# FTDI.net
KiCad netlist of a schematic drawn in Altium Designer
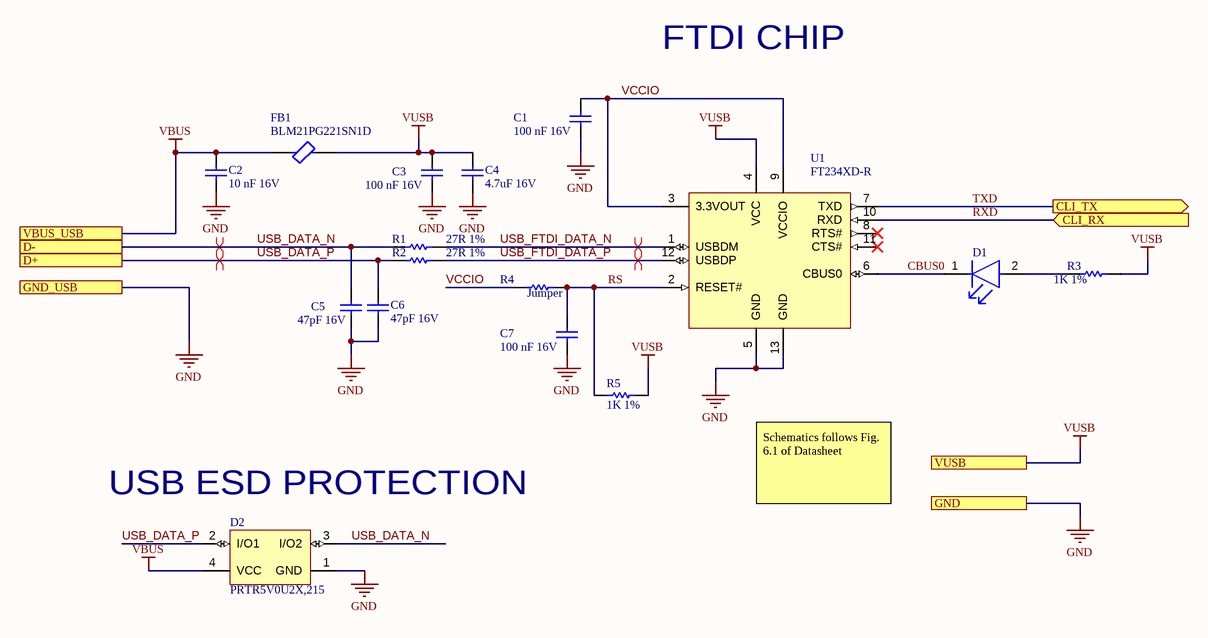
[diagram p0: FTDI.SchDoc]

(export (version "E")
  (design (tool "Eeschema 10.0.6"))
  (components
    (comp (ref "C1")
      (value "100 nF 16V")
      (footprint "CAPC1608X95X40LL15T15")
      (description "VJ0603Y104KXJCW1BC")
      (fields (field (name "MANUFACTURER") "Vitramon"))
      (libsource (lib "Altium Content Vault") (part "CAP"))
    )
    (comp (ref "C2")
      (value "10 nF 16V")
      (footprint "CAPC1608X87X35NL15T15")
      (description "C0603C103K4RACTU")
      (fields (field (name "MANUFACTURER") "Kemet"))
      (libsource (lib "Altium Content Vault") (part "CAP"))
    )
    (comp (ref "C3")
      (value "100 nF 16V")
      (footprint "CAPC1608X95X40LL15T15")
      (description "VJ0603Y104KXJCW1BC")
      (fields (field (name "MANUFACTURER") "Vitramon"))
      (libsource (lib "Altium Content Vault") (part "CAP"))
    )
    (comp (ref "C4")
      (value "4.7uF 16V")
      (footprint "CAPC0805(2012)145_N")
      (description "CAP 4.7uF 16V -20% to +80% 0805 (2012 Metric) Thickness 1.45mm SMD")
      (fields (field (name "TOLERANCE") "-20% to +80%"))
      (libsource (lib "Altium Content Vault") (part "CAP"))
    )
    (comp (ref "C5")
      (value "47pF 16V")
      (footprint "CAPC0603(1608)100_N")
      (description "CAP 47pF 16V ±0.5pF 0603 (1608 Metric) Thickness 1mm SMD")
      (fields (field (name "TOLERANCE") "Â±0.5pF"))
      (libsource (lib "Altium Content Vault") (part "CAP"))
    )
    (comp (ref "C6")
      (value "47pF 16V")
      (footprint "CAPC0603(1608)100_N")
      (description "CAP 47pF 16V ±0.5pF 0603 (1608 Metric) Thickness 1mm SMD")
      (fields (field (name "TOLERANCE") "Â±0.5pF"))
      (libsource (lib "Altium Content Vault") (part "CAP"))
    )
    (comp (ref "C7")
      (value "100 nF 16V")
      (footprint "CAPC1608X95X40LL15T15")
      (description "VJ0603Y104KXJCW1BC")
      (fields (field (name "MANUFACTURER") "Vitramon"))
      (libsource (lib "Altium Content Vault") (part "CAP"))
    )
    (comp (ref "D1")
      (value "LTST-C170CKT")
      (footprint "FP-LTST-C170CKT-MFG")
      (description "LED RED CLEAR SMD")
      (fields (field (name "VOLTAGE") "5V"))
      (libsource (lib "Altium Content Vault") (part "8706943c75ba83719d021d2fdc84c58"))
    )
    (comp (ref "D2")
      (value "PRTR5V0U2X,215")
      (footprint "NXP-SOT143B-4_V")
      (fields (field (name "MANUFACTURER") "NXP Semiconductors"))
      (libsource (lib "Altium Content Vault") (part "NXP-PRTR5V0U2X,215-4"))
    )
    (comp (ref "FB1")
      (value "BLM21PG221SN1D")
      (footprint "FP-BLM21-0_2-t0_85-e0_5-IPC_A")
      (description "Chip Ferrite Bead, 0805, 220Ω @ 100MHz, 0.045Ω, 25%, 2A")
      (fields (field (name "TOLERANCE") "25%"))
      (libsource (lib "Altium Content Vault") (part "5f30dd21d616792df468990f7003faa"))
    )
    (comp (ref "R1")
      (value "27R 1%")
      (footprint "RESC0603(1608)_N")
      (description "27R 0.1W 1% 0603 (1608 Metric)  SMD")
      (fields (field (name "TOLERANCE") "1 %") (field (name "POWER") "0.1 W"))
      (libsource (lib "Altium Content Vault") (part "RES"))
    )
    (comp (ref "R2")
      (value "27R 1%")
      (footprint "RESC0603(1608)_N")
      (description "27R 0.1W 1% 0603 (1608 Metric)  SMD")
      (fields (field (name "TOLERANCE") "1 %") (field (name "POWER") "0.1 W"))
      (libsource (lib "Altium Content Vault") (part "RES"))
    )
    (comp (ref "R3")
      (value "1K 1%")
      (footprint "RESC1609X50X30LL10T20")
      (description "CRCW06031K00FKEB")
      (fields (field (name "MANUFACTURER") "Vishay Dale"))
      (libsource (lib "Altium Content Vault") (part "RES"))
    )
    (comp (ref "R4")
      (value "Jumper")
      (footprint "RESC1609X50X30LL10T20")
      (fields (field (name "MANUFACTURER") "Vishay Dale") (field (name "PART NUMBER") "CRCW06030000Z0EC"))
      (libsource (lib "Altium Content Vault") (part "RES"))
    )
    (comp (ref "R5")
      (value "1K 1%")
      (footprint "RESC1609X50X30LL10T20")
      (description "CRCW06031K00FKEB")
      (fields (field (name "MANUFACTURER") "Vishay Dale"))
      (libsource (lib "Altium Content Vault") (part "RES"))
    )
    (comp (ref "U1")
      (value "FT234XD-R")
      (footprint "DFN-12_V")
      (description "FT234XD USB to BASIC UART IC, -40 to +85 degC, 12-Pin DFN, Pb-Free, Tape and Reel")
      (fields (field (name "MANUFACTURER") "FTDI"))
      (libsource (lib "Altium Content Vault") (part "FTDI-FT234XD-DFN-12"))
    )
  )
  (nets
    (net (code "1") (name "/CBUS0") (class "Default")
      (node (ref "D1") (pin "1") (pinfunction "C_1") (pintype "passive"))
      (node (ref "U1") (pin "6") (pinfunction "CBUS0_6") (pintype "bidirectional"))
    )
    (net (code "2") (name "/RS") (class "Default")
      (node (ref "C7") (pin "2") (pinfunction "2_2") (pintype "passive"))
      (node (ref "R4") (pin "2") (pinfunction "2_2") (pintype "passive"))
      (node (ref "R5") (pin "2") (pinfunction "2_2") (pintype "passive"))
      (node (ref "U1") (pin "2") (pinfunction "RESET#_2") (pintype "input"))
    )
    (net (code "3") (name "/RXD") (class "Default")
      (node (ref "U1") (pin "10") (pinfunction "RXD_10") (pintype "input"))
    )
    (net (code "4") (name "/TXD") (class "Default")
      (node (ref "U1") (pin "7") (pinfunction "TXD_7") (pintype "output"))
    )
    (net (code "5") (name "/USB_DATA_N") (class "Default")
      (node (ref "C5") (pin "2") (pinfunction "2_2") (pintype "passive"))
      (node (ref "D2") (pin "3") (pinfunction "I/O2_3") (pintype "bidirectional"))
      (node (ref "R1") (pin "1") (pinfunction "1_1") (pintype "passive"))
    )
    (net (code "6") (name "/USB_DATA_P") (class "Default")
      (node (ref "C6") (pin "2") (pinfunction "2_2") (pintype "passive"))
      (node (ref "D2") (pin "2") (pinfunction "I/O1_2") (pintype "bidirectional"))
      (node (ref "R2") (pin "1") (pinfunction "1_1") (pintype "passive"))
    )
    (net (code "7") (name "/USB_FTDI_DATA_N") (class "Default")
      (node (ref "R1") (pin "2") (pinfunction "2_2") (pintype "passive"))
      (node (ref "U1") (pin "1") (pinfunction "USBDM_1") (pintype "bidirectional"))
    )
    (net (code "8") (name "/USB_FTDI_DATA_P") (class "Default")
      (node (ref "R2") (pin "2") (pinfunction "2_2") (pintype "passive"))
      (node (ref "U1") (pin "12") (pinfunction "USBDP_12") (pintype "bidirectional"))
    )
    (net (code "9") (name "/VCCIO") (class "Default")
      (node (ref "C1") (pin "2") (pinfunction "2_2") (pintype "passive"))
      (node (ref "R4") (pin "1") (pinfunction "1_1") (pintype "passive"))
      (node (ref "U1") (pin "3") (pinfunction "3.3VOUT_3") (pintype "power_in"))
      (node (ref "U1") (pin "9") (pinfunction "VCCIO_9") (pintype "power_in"))
    )
    (net (code "10") (name "GND") (class "Default")
      (node (ref "C1") (pin "1") (pinfunction "1_1") (pintype "passive"))
      (node (ref "C2") (pin "1") (pinfunction "1_1") (pintype "passive"))
      (node (ref "C3") (pin "1") (pinfunction "1_1") (pintype "passive"))
      (node (ref "C4") (pin "1") (pinfunction "1_1") (pintype "passive"))
      (node (ref "C5") (pin "1") (pinfunction "1_1") (pintype "passive"))
      (node (ref "C6") (pin "1") (pinfunction "1_1") (pintype "passive"))
      (node (ref "C7") (pin "1") (pinfunction "1_1") (pintype "passive"))
      (node (ref "D2") (pin "1") (pinfunction "GND_1") (pintype "power_in"))
      (node (ref "U1") (pin "13") (pinfunction "GND_13") (pintype "power_in"))
      (node (ref "U1") (pin "5") (pinfunction "GND_5") (pintype "power_in"))
    )
    (net (code "11") (name "Net-(D1-A)") (class "Default")
      (node (ref "D1") (pin "2") (pinfunction "A_2") (pintype "passive"))
      (node (ref "R3") (pin "1") (pinfunction "1_1") (pintype "passive"))
    )
    (net (code "12") (name "VBUS") (class "Default")
      (node (ref "C2") (pin "2") (pinfunction "2_2") (pintype "passive"))
      (node (ref "D2") (pin "4") (pinfunction "VCC_4") (pintype "power_in"))
      (node (ref "FB1") (pin "1") (pinfunction "1_1") (pintype "passive"))
    )
    (net (code "13") (name "VUSB") (class "Default")
      (node (ref "C3") (pin "2") (pinfunction "2_2") (pintype "passive"))
      (node (ref "C4") (pin "2") (pinfunction "2_2") (pintype "passive"))
      (node (ref "FB1") (pin "2") (pinfunction "2_2") (pintype "passive"))
      (node (ref "R3") (pin "2") (pinfunction "2_2") (pintype "passive"))
      (node (ref "R5") (pin "1") (pinfunction "1_1") (pintype "passive"))
      (node (ref "U1") (pin "4") (pinfunction "VCC_4") (pintype "power_in"))
    )
    (net (code "14") (name "unconnected-(U1-CTS#-Pad11)") (class "Default")
      (node (ref "U1") (pin "11") (pinfunction "CTS#_11") (pintype "input+no_connect"))
    )
    (net (code "15") (name "unconnected-(U1-RTS#-Pad8)") (class "Default")
      (node (ref "U1") (pin "8") (pinfunction "RTS#_8") (pintype "output+no_connect"))
    )
  )
)
